# hdmilight-Duo.net
KiCad netlist of a schematic drawn in EAGLE
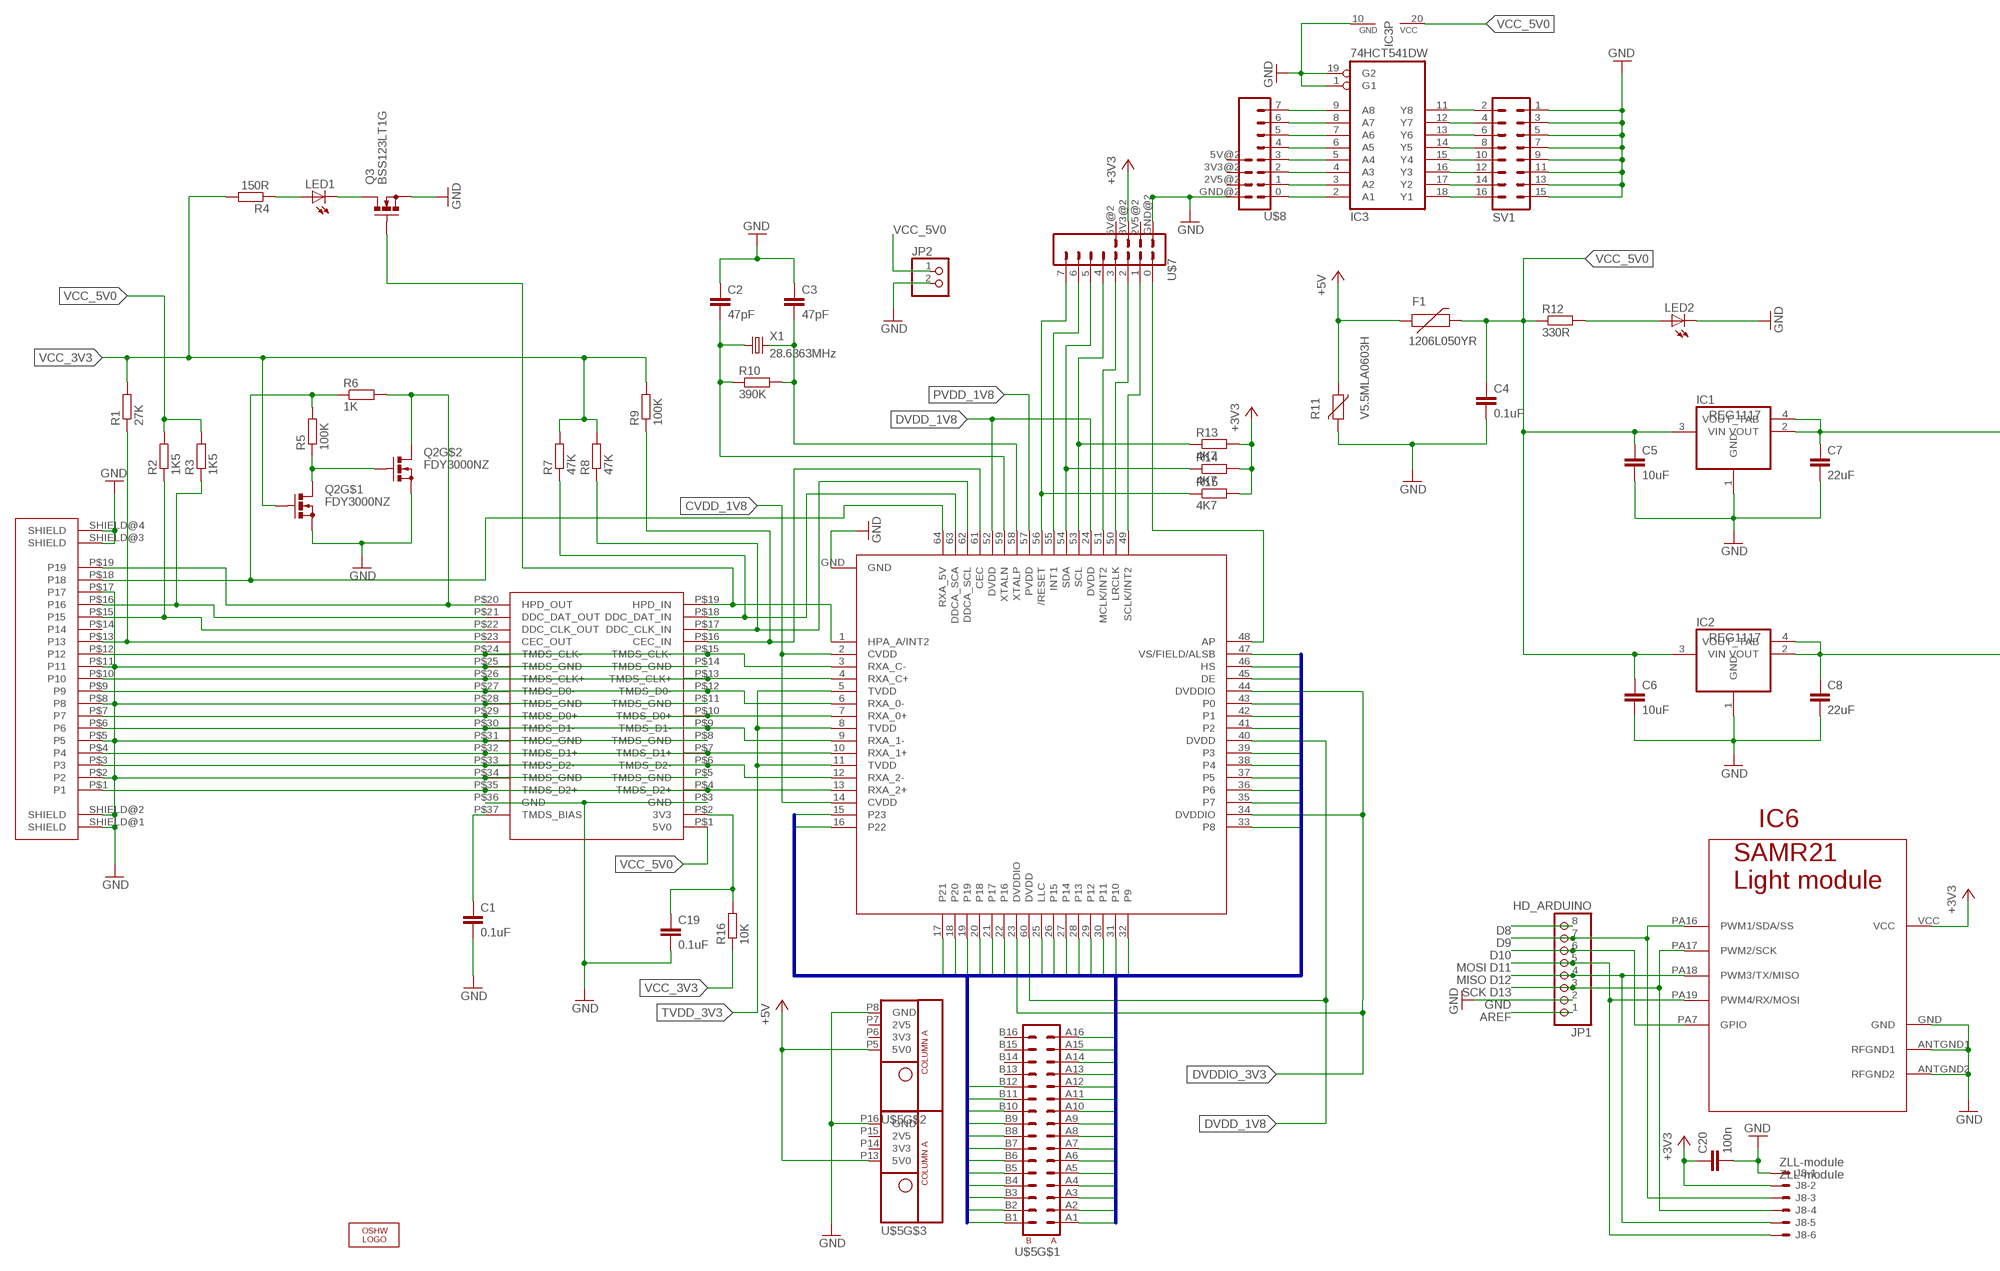
[diagram p0: schematic, sheet 1, part 1 of 2]
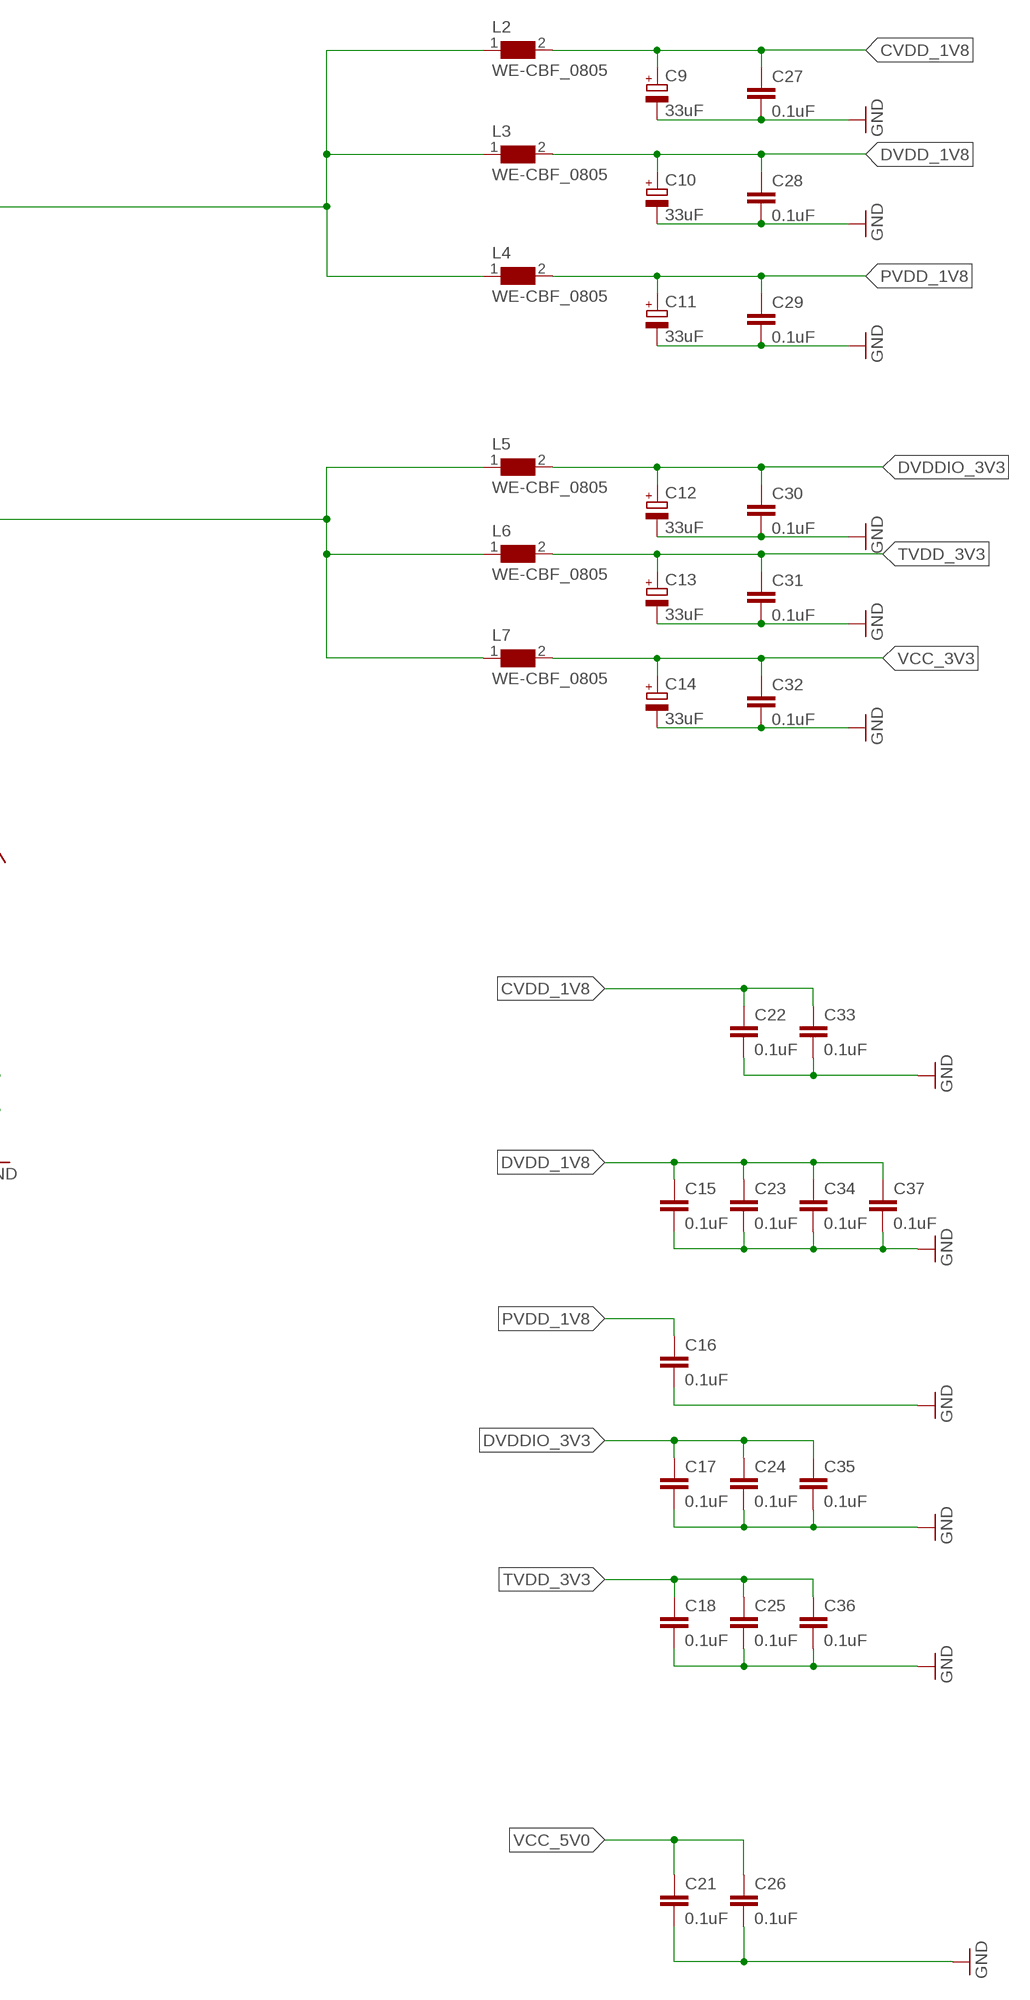
[diagram p1: schematic, sheet 1, part 2 of 2]

(export (version "E")
  (design (tool "Eeschema 10.0.6"))
  (components
    (comp (ref "C1")
      (value "0.1uF")
      (footprint "eagle-import:C0603")
      (libsource (lib "eagle-import") (part "resistor_C-EUC0603"))
    )
    (comp (ref "C2")
      (value "47pF")
      (footprint "eagle-import:C0603")
      (libsource (lib "eagle-import") (part "resistor_C-EUC0603"))
    )
    (comp (ref "C3")
      (value "47pF")
      (footprint "eagle-import:C0603")
      (libsource (lib "eagle-import") (part "resistor_C-EUC0603"))
    )
    (comp (ref "C4")
      (value "0.1uF")
      (footprint "eagle-import:C0603")
      (libsource (lib "eagle-import") (part "resistor_C-EUC0603"))
    )
    (comp (ref "C5")
      (value "10uF")
      (footprint "eagle-import:C1210")
      (libsource (lib "eagle-import") (part "resistor_C-EUC1210"))
    )
    (comp (ref "C6")
      (value "10uF")
      (footprint "eagle-import:C1210")
      (libsource (lib "eagle-import") (part "resistor_C-EUC1210"))
    )
    (comp (ref "C7")
      (value "22uF")
      (footprint "eagle-import:C1206")
      (libsource (lib "eagle-import") (part "resistor_C-EUC1206"))
    )
    (comp (ref "C8")
      (value "22uF")
      (footprint "eagle-import:C1206")
      (libsource (lib "eagle-import") (part "resistor_C-EUC1206"))
    )
    (comp (ref "C9")
      (value "33uF")
      (footprint "eagle-import:SMC_B")
      (libsource (lib "eagle-import") (part "CPOL-EUSMCB"))
    )
    (comp (ref "C10")
      (value "33uF")
      (footprint "eagle-import:SMC_B")
      (libsource (lib "eagle-import") (part "CPOL-EUSMCB"))
    )
    (comp (ref "C11")
      (value "33uF")
      (footprint "eagle-import:SMC_B")
      (libsource (lib "eagle-import") (part "CPOL-EUSMCB"))
    )
    (comp (ref "C12")
      (value "33uF")
      (footprint "eagle-import:SMC_B")
      (libsource (lib "eagle-import") (part "CPOL-EUSMCB"))
    )
    (comp (ref "C13")
      (value "33uF")
      (footprint "eagle-import:SMC_B")
      (libsource (lib "eagle-import") (part "CPOL-EUSMCB"))
    )
    (comp (ref "C14")
      (value "33uF")
      (footprint "eagle-import:SMC_B")
      (libsource (lib "eagle-import") (part "CPOL-EUSMCB"))
    )
    (comp (ref "C15")
      (value "0.1uF")
      (footprint "eagle-import:C0402")
      (libsource (lib "eagle-import") (part "resistor_C-EUC0402"))
    )
    (comp (ref "C16")
      (value "0.1uF")
      (footprint "eagle-import:C0603")
      (libsource (lib "eagle-import") (part "resistor_C-EUC0603"))
    )
    (comp (ref "C17")
      (value "0.1uF")
      (footprint "eagle-import:C0603")
      (libsource (lib "eagle-import") (part "resistor_C-EUC0603"))
    )
    (comp (ref "C18")
      (value "0.1uF")
      (footprint "eagle-import:C0402")
      (libsource (lib "eagle-import") (part "resistor_C-EUC0402"))
    )
    (comp (ref "C19")
      (value "0.1uF")
      (footprint "eagle-import:C0603")
      (libsource (lib "eagle-import") (part "resistor_C-EUC0603"))
    )
    (comp (ref "C20")
      (value "100n")
      (footprint "eagle-import:C0603K")
      (libsource (lib "eagle-import") (part "C-EUC0603K"))
    )
    (comp (ref "C21")
      (value "0.1uF")
      (footprint "eagle-import:C0603")
      (libsource (lib "eagle-import") (part "resistor_C-EUC0603"))
    )
    (comp (ref "C22")
      (value "0.1uF")
      (footprint "eagle-import:C0603")
      (libsource (lib "eagle-import") (part "resistor_C-EUC0603"))
    )
    (comp (ref "C23")
      (value "0.1uF")
      (footprint "eagle-import:C0402")
      (libsource (lib "eagle-import") (part "resistor_C-EUC0402"))
    )
    (comp (ref "C24")
      (value "0.1uF")
      (footprint "eagle-import:C0603")
      (libsource (lib "eagle-import") (part "resistor_C-EUC0603"))
    )
    (comp (ref "C25")
      (value "0.1uF")
      (footprint "eagle-import:C0402")
      (libsource (lib "eagle-import") (part "resistor_C-EUC0402"))
    )
    (comp (ref "C26")
      (value "0.1uF")
      (footprint "eagle-import:C0603")
      (libsource (lib "eagle-import") (part "resistor_C-EUC0603"))
    )
    (comp (ref "C27")
      (value "0.1uF")
      (footprint "eagle-import:C0603")
      (libsource (lib "eagle-import") (part "resistor_C-EUC0603"))
    )
    (comp (ref "C28")
      (value "0.1uF")
      (footprint "eagle-import:C0603")
      (libsource (lib "eagle-import") (part "resistor_C-EUC0603"))
    )
    (comp (ref "C29")
      (value "0.1uF")
      (footprint "eagle-import:C0603")
      (libsource (lib "eagle-import") (part "resistor_C-EUC0603"))
    )
    (comp (ref "C30")
      (value "0.1uF")
      (footprint "eagle-import:C0603")
      (libsource (lib "eagle-import") (part "resistor_C-EUC0603"))
    )
    (comp (ref "C31")
      (value "0.1uF")
      (footprint "eagle-import:C0603")
      (libsource (lib "eagle-import") (part "resistor_C-EUC0603"))
    )
    (comp (ref "C32")
      (value "0.1uF")
      (footprint "eagle-import:C0603")
      (libsource (lib "eagle-import") (part "resistor_C-EUC0603"))
    )
    (comp (ref "C33")
      (value "0.1uF")
      (footprint "eagle-import:C0603")
      (libsource (lib "eagle-import") (part "resistor_C-EUC0603"))
    )
    (comp (ref "C34")
      (value "0.1uF")
      (footprint "eagle-import:C0402")
      (libsource (lib "eagle-import") (part "resistor_C-EUC0402"))
    )
    (comp (ref "C35")
      (value "0.1uF")
      (footprint "eagle-import:C0402")
      (libsource (lib "eagle-import") (part "resistor_C-EUC0402"))
    )
    (comp (ref "C36")
      (value "0.1uF")
      (footprint "eagle-import:C0402")
      (libsource (lib "eagle-import") (part "resistor_C-EUC0402"))
    )
    (comp (ref "C37")
      (value "0.1uF")
      (footprint "eagle-import:C0402")
      (libsource (lib "eagle-import") (part "resistor_C-EUC0402"))
    )
    (comp (ref "F1")
      (value "1206L050YR")
      (footprint "eagle-import:PTC-1206")
      (libsource (lib "eagle-import") (part "PTCSMD"))
    )
    (comp (ref "IC1")
      (value "REG1117")
      (footprint "eagle-import:SOT223")
      (libsource (lib "eagle-import") (part "REG1117"))
    )
    (comp (ref "IC2")
      (value "REG1117")
      (footprint "eagle-import:SOT223")
      (libsource (lib "eagle-import") (part "REG1117"))
    )
    (comp (ref "IC3")
      (value "74HCT541DW")
      (footprint "eagle-import:SO20W")
      (libsource (lib "eagle-import") (part "74541DWHCT"))
    )
    (comp (ref "IC4")
      (value "ADV7611")
      (footprint "eagle-import:TQFP64-10X10")
      (libsource (lib "eagle-import") (part "ADV7611"))
    )
    (comp (ref "IC5")
      (value "TPD12S520")
      (footprint "eagle-import:TSSOP38")
      (libsource (lib "eagle-import") (part "IP4776CZ38"))
    )
    (comp (ref "IC6")
      (value "SAMR21-MODLL")
      (footprint "eagle-import:SAMR21-LLMOD")
      (libsource (lib "eagle-import") (part "SAMR21-MODLL"))
    )
    (comp (ref "J1")
      (value "FCI_HDMI_SOCKET_10029449-001RCF")
      (footprint "eagle-import:FCI_HDMI_SOCKET_10029449-001RCF")
      (libsource (lib "eagle-import") (part "FCI_HDMI_SOCKET_10029449-001RCF"))
    )
    (comp (ref "J8")
      (value "ZLL-module")
      (footprint "eagle-import:331-06")
      (libsource (lib "eagle-import") (part "331-06"))
    )
    (comp (ref "JP1")
      (value "HD_ARDUINO")
      (footprint "eagle-import:1X08_OCT")
      (libsource (lib "eagle-import") (part "PINHD-1X8/OCT"))
    )
    (comp (ref "JP2")
      (value "PINHD-1X2/OCT")
      (footprint "eagle-import:1X02_OCT")
      (libsource (lib "eagle-import") (part "PINHD-1X2/OCT"))
    )
    (comp (ref "L2")
      (value "WE-CBF_0805")
      (footprint "eagle-import:0805")
      (libsource (lib "eagle-import") (part "WE-CBF_0805"))
    )
    (comp (ref "L3")
      (value "WE-CBF_0805")
      (footprint "eagle-import:0805")
      (libsource (lib "eagle-import") (part "WE-CBF_0805"))
    )
    (comp (ref "L4")
      (value "WE-CBF_0805")
      (footprint "eagle-import:0805")
      (libsource (lib "eagle-import") (part "WE-CBF_0805"))
    )
    (comp (ref "L5")
      (value "WE-CBF_0805")
      (footprint "eagle-import:0805")
      (libsource (lib "eagle-import") (part "WE-CBF_0805"))
    )
    (comp (ref "L6")
      (value "WE-CBF_0805")
      (footprint "eagle-import:0805")
      (libsource (lib "eagle-import") (part "WE-CBF_0805"))
    )
    (comp (ref "L7")
      (value "WE-CBF_0805")
      (footprint "eagle-import:0805")
      (libsource (lib "eagle-import") (part "WE-CBF_0805"))
    )
    (comp (ref "LED1")
      (value "LEDCHIP-LED0805")
      (footprint "eagle-import:CHIP-LED0805")
      (libsource (lib "eagle-import") (part "LEDCHIP-LED0805"))
    )
    (comp (ref "LED2")
      (value "LEDCHIP-LED0805")
      (footprint "eagle-import:CHIP-LED0805")
      (libsource (lib "eagle-import") (part "LEDCHIP-LED0805"))
    )
    (comp (ref "LOGO1")
      (value "OSHW_LOGO_FILLX0200-NT")
      (footprint "eagle-import:OSHW_FILLX200_NOTEXT")
      (libsource (lib "eagle-import") (part "OSHW_LOGO_FILLX0200-NT"))
    )
    (comp (ref "Q2")
      (value "FDY3000NZ")
      (footprint "eagle-import:SC89-6")
      (libsource (lib "eagle-import") (part "FDY3000NZ"))
    )
    (comp (ref "Q3")
      (value "BSS123LT1G")
      (footprint "eagle-import:SOT23")
      (libsource (lib "eagle-import") (part "BSS123LT1G"))
    )
    (comp (ref "R1")
      (value "27K")
      (footprint "eagle-import:R0603")
      (libsource (lib "eagle-import") (part "R-EU_R0603"))
    )
    (comp (ref "R2")
      (value "1K5")
      (footprint "eagle-import:R0603")
      (libsource (lib "eagle-import") (part "R-EU_R0603"))
    )
    (comp (ref "R3")
      (value "1K5")
      (footprint "eagle-import:R0603")
      (libsource (lib "eagle-import") (part "R-EU_R0603"))
    )
    (comp (ref "R4")
      (value "150R")
      (footprint "eagle-import:R0603")
      (libsource (lib "eagle-import") (part "R-EU_R0603"))
    )
    (comp (ref "R5")
      (value "100K")
      (footprint "eagle-import:R0603")
      (libsource (lib "eagle-import") (part "R-EU_R0603"))
    )
    (comp (ref "R6")
      (value "1K")
      (footprint "eagle-import:R0603")
      (libsource (lib "eagle-import") (part "R-EU_R0603"))
    )
    (comp (ref "R7")
      (value "47K")
      (footprint "eagle-import:R0603")
      (libsource (lib "eagle-import") (part "R-EU_R0603"))
    )
    (comp (ref "R8")
      (value "47K")
      (footprint "eagle-import:R0603")
      (libsource (lib "eagle-import") (part "R-EU_R0603"))
    )
    (comp (ref "R9")
      (value "100K")
      (footprint "eagle-import:R0603")
      (libsource (lib "eagle-import") (part "R-EU_R0603"))
    )
    (comp (ref "R10")
      (value "390K")
      (footprint "eagle-import:R0603")
      (libsource (lib "eagle-import") (part "R-EU_R0603"))
    )
    (comp (ref "R11")
      (value "V5.5MLA0603H")
      (footprint "eagle-import:CT_CN0603")
      (libsource (lib "eagle-import") (part "VARISTORCN0603"))
    )
    (comp (ref "R12")
      (value "330R")
      (footprint "eagle-import:R0603")
      (libsource (lib "eagle-import") (part "R-EU_R0603"))
    )
    (comp (ref "R13")
      (value "4K7")
      (footprint "eagle-import:R0603")
      (libsource (lib "eagle-import") (part "R-EU_R0603"))
    )
    (comp (ref "R14")
      (value "4K7")
      (footprint "eagle-import:R0603")
      (libsource (lib "eagle-import") (part "R-EU_R0603"))
    )
    (comp (ref "R15")
      (value "4K7")
      (footprint "eagle-import:R0603")
      (libsource (lib "eagle-import") (part "R-EU_R0603"))
    )
    (comp (ref "R16")
      (value "10K")
      (footprint "eagle-import:R0603")
      (libsource (lib "eagle-import") (part "R-EU_R0603"))
    )
    (comp (ref "SV1")
      (value "MA08-2")
      (footprint "eagle-import:MA08-2")
      (libsource (lib "eagle-import") (part "MA08-2"))
    )
    (comp (ref "U$5")
      (value "WING32_HALF")
      (footprint "eagle-import:WING32_HALF_NOHOLES")
      (libsource (lib "eagle-import") (part "WING32_HALF"))
    )
    (comp (ref "U$7")
      (value "WING8WING8_NOHOLES")
      (footprint "eagle-import:WINGSIDE_8BIT_NOHOLES")
      (libsource (lib "eagle-import") (part "WING8WING8_NOHOLES"))
    )
    (comp (ref "U$8")
      (value "WING8WING8_NOHOLES")
      (footprint "eagle-import:WINGSIDE_8BIT_NOHOLES")
      (libsource (lib "eagle-import") (part "WING8WING8_NOHOLES"))
    )
    (comp (ref "X1")
      (value "28.6363MHz")
      (footprint "eagle-import:SM49")
      (libsource (lib "eagle-import") (part "CRYSTALSM49"))
    )
  )
  (nets
    (net (code "1") (name "+3V3") (class "Default")
      (node (ref "C20") (pin "1") (pinfunction "1_1") (pintype "passive"))
      (node (ref "IC6") (pin "VCC") (pinfunction "VCC_VCC") (pintype "bidirectional"))
      (node (ref "J8") (pin "3") (pinfunction "S_3") (pintype "passive"))
      (node (ref "R13") (pin "2") (pinfunction "2_2") (pintype "passive"))
      (node (ref "R14") (pin "2") (pinfunction "2_2") (pintype "passive"))
      (node (ref "R15") (pin "2") (pinfunction "2_2") (pintype "passive"))
      (node (ref "U$7") (pin "3V3@2") (pinfunction "3V3_3V3@2") (pintype "passive"))
    )
    (net (code "2") (name "+5V") (class "Default")
      (node (ref "F1") (pin "1") (pinfunction "1_1") (pintype "bidirectional"))
      (node (ref "R11") (pin "1") (pinfunction "1_1") (pintype "passive"))
      (node (ref "U$5") (pin "P13") (pinfunction "5V0_P13") (pintype "passive"))
      (node (ref "U$5") (pin "P5") (pinfunction "5V0_P5") (pintype "passive"))
    )
    (net (code "3") (name "/AREF") (class "Default")
      (node (ref "JP1") (pin "1") (pinfunction "1_1") (pintype "passive"))
    )
    (net (code "4") (name "/D8") (class "Default")
      (node (ref "JP1") (pin "8") (pinfunction "8_8") (pintype "passive"))
    )
    (net (code "5") (name "/D9") (class "Default")
      (node (ref "IC6") (pin "PA16") (pinfunction "PWM1/SDA/SS_PA16") (pintype "bidirectional"))
      (node (ref "J8") (pin "5") (pinfunction "S_5") (pintype "passive"))
      (node (ref "JP1") (pin "7") (pinfunction "7_7") (pintype "passive"))
    )
    (net (code "6") (name "/D10") (class "Default")
      (node (ref "IC6") (pin "PA7") (pinfunction "GPIO_PA7") (pintype "bidirectional"))
      (node (ref "JP1") (pin "6") (pinfunction "6_6") (pintype "passive"))
    )
    (net (code "7") (name "/D11") (class "Default")
      (node (ref "IC6") (pin "PA19") (pinfunction "PWM4/RX/MOSI_PA19") (pintype "bidirectional"))
      (node (ref "J8") (pin "11") (pinfunction "S_11") (pintype "passive"))
      (node (ref "JP1") (pin "5") (pinfunction "5_5") (pintype "passive"))
    )
    (net (code "8") (name "/D12") (class "Default")
      (node (ref "IC6") (pin "PA18") (pinfunction "PWM3/TX/MISO_PA18") (pintype "bidirectional"))
      (node (ref "J8") (pin "9") (pinfunction "S_9") (pintype "passive"))
      (node (ref "JP1") (pin "4") (pinfunction "4_4") (pintype "passive"))
    )
    (net (code "9") (name "/D13") (class "Default")
      (node (ref "IC6") (pin "PA17") (pinfunction "PWM2/SCK_PA17") (pintype "bidirectional"))
      (node (ref "J8") (pin "7") (pinfunction "S_7") (pintype "passive"))
      (node (ref "JP1") (pin "3") (pinfunction "3_3") (pintype "passive"))
    )
    (net (code "10") (name "/DE") (class "Default")
      (node (ref "IC4") (pin "45") (pinfunction "DE_45") (pintype "bidirectional"))
      (node (ref "U$5") (pin "B2") (pinfunction "B2_B2") (pintype "bidirectional"))
    )
    (net (code "11") (name "/HS") (class "Default")
      (node (ref "IC4") (pin "46") (pinfunction "HS_46") (pintype "bidirectional"))
      (node (ref "U$5") (pin "A1") (pinfunction "A1_A1") (pintype "bidirectional"))
    )
    (net (code "12") (name "/LLC") (class "Default")
      (node (ref "IC4") (pin "25") (pinfunction "LLC_25") (pintype "bidirectional"))
      (node (ref "U$5") (pin "A14") (pinfunction "A14_A14") (pintype "bidirectional"))
    )
    (net (code "13") (name "/P0") (class "Default")
      (node (ref "IC4") (pin "43") (pinfunction "P0_43") (pintype "bidirectional"))
      (node (ref "U$5") (pin "A2") (pinfunction "A2_A2") (pintype "bidirectional"))
    )
    (net (code "14") (name "/P1") (class "Default")
      (node (ref "IC4") (pin "42") (pinfunction "P1_42") (pintype "bidirectional"))
      (node (ref "U$5") (pin "B3") (pinfunction "B3_B3") (pintype "bidirectional"))
    )
    (net (code "15") (name "/P2") (class "Default")
      (node (ref "IC4") (pin "41") (pinfunction "P2_41") (pintype "bidirectional"))
      (node (ref "U$5") (pin "A3") (pinfunction "A3_A3") (pintype "bidirectional"))
    )
    (net (code "16") (name "/P3") (class "Default")
      (node (ref "IC4") (pin "39") (pinfunction "P3_39") (pintype "bidirectional"))
      (node (ref "U$5") (pin "B4") (pinfunction "B4_B4") (pintype "bidirectional"))
    )
    (net (code "17") (name "/P4") (class "Default")
      (node (ref "IC4") (pin "38") (pinfunction "P4_38") (pintype "bidirectional"))
      (node (ref "U$5") (pin "A4") (pinfunction "A4_A4") (pintype "bidirectional"))
    )
    (net (code "18") (name "/P5") (class "Default")
      (node (ref "IC4") (pin "37") (pinfunction "P5_37") (pintype "bidirectional"))
      (node (ref "U$5") (pin "B5") (pinfunction "B5_B5") (pintype "bidirectional"))
    )
    (net (code "19") (name "/P6") (class "Default")
      (node (ref "IC4") (pin "36") (pinfunction "P6_36") (pintype "bidirectional"))
      (node (ref "U$5") (pin "A5") (pinfunction "A5_A5") (pintype "bidirectional"))
    )
    (net (code "20") (name "/P7") (class "Default")
      (node (ref "IC4") (pin "35") (pinfunction "P7_35") (pintype "bidirectional"))
      (node (ref "U$5") (pin "B6") (pinfunction "B6_B6") (pintype "bidirectional"))
    )
    (net (code "21") (name "/P8") (class "Default")
      (node (ref "IC4") (pin "33") (pinfunction "P8_33") (pintype "bidirectional"))
      (node (ref "U$5") (pin "A6") (pinfunction "A6_A6") (pintype "bidirectional"))
    )
    (net (code "22") (name "/P9") (class "Default")
      (node (ref "IC4") (pin "32") (pinfunction "P9_32") (pintype "bidirectional"))
      (node (ref "U$5") (pin "B7") (pinfunction "B7_B7") (pintype "bidirectional"))
    )
    (net (code "23") (name "/P10") (class "Default")
      (node (ref "IC4") (pin "31") (pinfunction "P10_31") (pintype "bidirectional"))
      (node (ref "U$5") (pin "A7") (pinfunction "A7_A7") (pintype "bidirectional"))
    )
    (net (code "24") (name "/P11") (class "Default")
      (node (ref "IC4") (pin "30") (pinfunction "P11_30") (pintype "bidirectional"))
      (node (ref "U$5") (pin "B8") (pinfunction "B8_B8") (pintype "bidirectional"))
    )
    (net (code "25") (name "/P12") (class "Default")
      (node (ref "IC4") (pin "29") (pinfunction "P12_29") (pintype "bidirectional"))
      (node (ref "U$5") (pin "A8") (pinfunction "A8_A8") (pintype "bidirectional"))
    )
    (net (code "26") (name "/P13") (class "Default")
      (node (ref "IC4") (pin "28") (pinfunction "P13_28") (pintype "bidirectional"))
      (node (ref "U$5") (pin "B9") (pinfunction "B9_B9") (pintype "bidirectional"))
    )
    (net (code "27") (name "/P14") (class "Default")
      (node (ref "IC4") (pin "27") (pinfunction "P14_27") (pintype "bidirectional"))
      (node (ref "U$5") (pin "A9") (pinfunction "A9_A9") (pintype "bidirectional"))
    )
    (net (code "28") (name "/P15") (class "Default")
      (node (ref "IC4") (pin "26") (pinfunction "P15_26") (pintype "bidirectional"))
      (node (ref "U$5") (pin "B10") (pinfunction "B10_B10") (pintype "bidirectional"))
    )
    (net (code "29") (name "/P16") (class "Default")
      (node (ref "IC4") (pin "22") (pinfunction "P16_22") (pintype "bidirectional"))
      (node (ref "U$5") (pin "A10") (pinfunction "A10_A10") (pintype "bidirectional"))
    )
    (net (code "30") (name "/P17") (class "Default")
      (node (ref "IC4") (pin "21") (pinfunction "P17_21") (pintype "bidirectional"))
      (node (ref "U$5") (pin "B11") (pinfunction "B11_B11") (pintype "bidirectional"))
    )
    (net (code "31") (name "/P18") (class "Default")
      (node (ref "IC4") (pin "20") (pinfunction "P18_20") (pintype "bidirectional"))
      (node (ref "U$5") (pin "A11") (pinfunction "A11_A11") (pintype "bidirectional"))
    )
    (net (code "32") (name "/P19") (class "Default")
      (node (ref "IC4") (pin "19") (pinfunction "P19_19") (pintype "bidirectional"))
      (node (ref "U$5") (pin "B12") (pinfunction "B12_B12") (pintype "bidirectional"))
    )
    (net (code "33") (name "/P20") (class "Default")
      (node (ref "IC4") (pin "18") (pinfunction "P20_18") (pintype "bidirectional"))
      (node (ref "U$5") (pin "A12") (pinfunction "A12_A12") (pintype "bidirectional"))
    )
    (net (code "34") (name "/P21") (class "Default")
      (node (ref "IC4") (pin "17") (pinfunction "P21_17") (pintype "bidirectional"))
      (node (ref "U$5") (pin "A13") (pinfunction "A13_A13") (pintype "bidirectional"))
    )
    (net (code "35") (name "/P22") (class "Default")
      (node (ref "IC4") (pin "16") (pinfunction "P22_16") (pintype "bidirectional"))
      (node (ref "U$5") (pin "A15") (pinfunction "A15_A15") (pintype "bidirectional"))
    )
    (net (code "36") (name "/P23") (class "Default")
      (node (ref "IC4") (pin "15") (pinfunction "P23_15") (pintype "bidirectional"))
      (node (ref "U$5") (pin "A16") (pinfunction "A16_A16") (pintype "bidirectional"))
    )
    (net (code "37") (name "/VS") (class "Default")
      (node (ref "IC4") (pin "47") (pinfunction "VS/FIELD/ALSB_47") (pintype "bidirectional"))
      (node (ref "U$5") (pin "B1") (pinfunction "B1_B1") (pintype "bidirectional"))
    )
    (net (code "38") (name "CVDD_1V8") (class "Default")
      (node (ref "C22") (pin "1") (pinfunction "1_1") (pintype "passive"))
      (node (ref "C27") (pin "1") (pinfunction "1_1") (pintype "passive"))
      (node (ref "C33") (pin "1") (pinfunction "1_1") (pintype "passive"))
      (node (ref "C9") (pin "+") (pinfunction "+_+") (pintype "passive"))
      (node (ref "IC4") (pin "14") (pinfunction "CVDD_14") (pintype "bidirectional"))
      (node (ref "IC4") (pin "2") (pinfunction "CVDD_2") (pintype "bidirectional"))
      (node (ref "L2") (pin "2") (pinfunction "2_2") (pintype "passive"))
    )
    (net (code "39") (name "DVDDIO_3V3") (class "Default")
      (node (ref "C12") (pin "+") (pinfunction "+_+") (pintype "passive"))
      (node (ref "C17") (pin "1") (pinfunction "1_1") (pintype "passive"))
      (node (ref "C24") (pin "1") (pinfunction "1_1") (pintype "passive"))
      (node (ref "C30") (pin "1") (pinfunction "1_1") (pintype "passive"))
      (node (ref "C35") (pin "1") (pinfunction "1_1") (pintype "passive"))
      (node (ref "IC4") (pin "23") (pinfunction "DVDDIO_23") (pintype "bidirectional"))
      (node (ref "IC4") (pin "34") (pinfunction "DVDDIO_34") (pintype "bidirectional"))
      (node (ref "IC4") (pin "44") (pinfunction "DVDDIO_44") (pintype "bidirectional"))
      (node (ref "L5") (pin "2") (pinfunction "2_2") (pintype "passive"))
    )
    (net (code "40") (name "DVDD_1V8") (class "Default")
      (node (ref "C10") (pin "+") (pinfunction "+_+") (pintype "passive"))
      (node (ref "C15") (pin "1") (pinfunction "1_1") (pintype "passive"))
      (node (ref "C23") (pin "1") (pinfunction "1_1") (pintype "passive"))
      (node (ref "C28") (pin "1") (pinfunction "1_1") (pintype "passive"))
      (node (ref "C34") (pin "1") (pinfunction "1_1") (pintype "passive"))
      (node (ref "C37") (pin "1") (pinfunction "1_1") (pintype "passive"))
      (node (ref "IC4") (pin "24") (pinfunction "DVDD_24") (pintype "bidirectional"))
      (node (ref "IC4") (pin "40") (pinfunction "DVDD_40") (pintype "bidirectional"))
      (node (ref "IC4") (pin "52") (pinfunction "DVDD_52") (pintype "bidirectional"))
      (node (ref "IC4") (pin "60") (pinfunction "DVDD_60") (pintype "bidirectional"))
      (node (ref "L3") (pin "2") (pinfunction "2_2") (pintype "passive"))
    )
    (net (code "41") (name "GND") (class "Default")
      (node (ref "C1") (pin "2") (pinfunction "2_2") (pintype "passive"))
      (node (ref "C10") (pin "-") (pinfunction "-_-") (pintype "passive"))
      (node (ref "C11") (pin "-") (pinfunction "-_-") (pintype "passive"))
      (node (ref "C12") (pin "-") (pinfunction "-_-") (pintype "passive"))
      (node (ref "C13") (pin "-") (pinfunction "-_-") (pintype "passive"))
      (node (ref "C14") (pin "-") (pinfunction "-_-") (pintype "passive"))
      (node (ref "C15") (pin "2") (pinfunction "2_2") (pintype "passive"))
      (node (ref "C16") (pin "2") (pinfunction "2_2") (pintype "passive"))
      (node (ref "C17") (pin "2") (pinfunction "2_2") (pintype "passive"))
      (node (ref "C18") (pin "2") (pinfunction "2_2") (pintype "passive"))
      (node (ref "C19") (pin "2") (pinfunction "2_2") (pintype "passive"))
      (node (ref "C2") (pin "1") (pinfunction "1_1") (pintype "passive"))
      (node (ref "C20") (pin "2") (pinfunction "2_2") (pintype "passive"))
      (node (ref "C21") (pin "2") (pinfunction "2_2") (pintype "passive"))
      (node (ref "C22") (pin "2") (pinfunction "2_2") (pintype "passive"))
      (node (ref "C23") (pin "2") (pinfunction "2_2") (pintype "passive"))
      (node (ref "C24") (pin "2") (pinfunction "2_2") (pintype "passive"))
      (node (ref "C25") (pin "2") (pinfunction "2_2") (pintype "passive"))
      (node (ref "C26") (pin "2") (pinfunction "2_2") (pintype "passive"))
      (node (ref "C27") (pin "2") (pinfunction "2_2") (pintype "passive"))
      (node (ref "C28") (pin "2") (pinfunction "2_2") (pintype "passive"))
      (node (ref "C29") (pin "2") (pinfunction "2_2") (pintype "passive"))
      (node (ref "C3") (pin "1") (pinfunction "1_1") (pintype "passive"))
      (node (ref "C30") (pin "2") (pinfunction "2_2") (pintype "passive"))
      (node (ref "C31") (pin "2") (pinfunction "2_2") (pintype "passive"))
      (node (ref "C32") (pin "2") (pinfunction "2_2") (pintype "passive"))
      (node (ref "C33") (pin "2") (pinfunction "2_2") (pintype "passive"))
      (node (ref "C34") (pin "2") (pinfunction "2_2") (pintype "passive"))
      (node (ref "C35") (pin "2") (pinfunction "2_2") (pintype "passive"))
      (node (ref "C36") (pin "2") (pinfunction "2_2") (pintype "passive"))
      (node (ref "C37") (pin "2") (pinfunction "2_2") (pintype "passive"))
      (node (ref "C4") (pin "2") (pinfunction "2_2") (pintype "passive"))
      (node (ref "C5") (pin "2") (pinfunction "2_2") (pintype "passive"))
      (node (ref "C6") (pin "2") (pinfunction "2_2") (pintype "passive"))
      (node (ref "C7") (pin "2") (pinfunction "2_2") (pintype "passive"))
      (node (ref "C8") (pin "2") (pinfunction "2_2") (pintype "passive"))
      (node (ref "C9") (pin "-") (pinfunction "-_-") (pintype "passive"))
      (node (ref "IC1") (pin "1") (pinfunction "GND_1") (pintype "power_in"))
      (node (ref "IC2") (pin "1") (pinfunction "GND_1") (pintype "power_in"))
      (node (ref "IC3") (pin "1") (pinfunction "G1_1") (pintype "input"))
      (node (ref "IC3") (pin "10") (pinfunction "GND_10") (pintype "power_in"))
      (node (ref "IC3") (pin "19") (pinfunction "G2_19") (pintype "input"))
      (node (ref "IC4") (pin "GND") (pinfunction "GND_GND") (pintype "bidirectional"))
      (node (ref "IC5") (pin "P$11") (pinfunction "TMDS_GND_P$11") (pintype "bidirectional"))
      (node (ref "IC5") (pin "P$14") (pinfunction "TMDS_GND_P$14") (pintype "bidirectional"))
      (node (ref "IC5") (pin "P$25") (pinfunction "TMDS_GND_P$25") (pintype "bidirectional"))
      (node (ref "IC5") (pin "P$28") (pinfunction "TMDS_GND_P$28") (pintype "bidirectional"))
      (node (ref "IC5") (pin "P$3") (pinfunction "GND_P$3") (pintype "bidirectional"))
      (node (ref "IC5") (pin "P$31") (pinfunction "TMDS_GND_P$31") (pintype "bidirectional"))
      (node (ref "IC5") (pin "P$34") (pinfunction "TMDS_GND_P$34") (pintype "bidirectional"))
      (node (ref "IC5") (pin "P$36") (pinfunction "GND_P$36") (pintype "bidirectional"))
      (node (ref "IC5") (pin "P$5") (pinfunction "TMDS_GND_P$5") (pintype "bidirectional"))
      (node (ref "IC5") (pin "P$8") (pinfunction "TMDS_GND_P$8") (pintype "bidirectional"))
      (node (ref "IC6") (pin "ANTGND1") (pinfunction "RFGND1_ANTGND1") (pintype "bidirectional"))
      (node (ref "IC6") (pin "ANTGND2") (pinfunction "RFGND2_ANTGND2") (pintype "bidirectional"))
      (node (ref "IC6") (pin "GND") (pinfunction "GND_GND") (pintype "bidirectional"))
      (node (ref "J1") (pin "P$11") (pinfunction "P11_P$11") (pintype "bidirectional"))
      (node (ref "J1") (pin "P$17") (pinfunction "P17_P$17") (pintype "bidirectional"))
      (node (ref "J1") (pin "P$2") (pinfunction "P2_P$2") (pintype "bidirectional"))
      (node (ref "J1") (pin "P$5") (pinfunction "P5_P$5") (pintype "bidirectional"))
      (node (ref "J1") (pin "P$8") (pinfunction "P8_P$8") (pintype "bidirectional"))
      (node (ref "J1") (pin "SHIELD@1") (pinfunction "SHIELD_SHIELD@1") (pintype "bidirectional"))
      (node (ref "J1") (pin "SHIELD@2") (pinfunction "SHIELD_SHIELD@2") (pintype "bidirectional"))
      (node (ref "J1") (pin "SHIELD@3") (pinfunction "SHIELD_SHIELD@3") (pintype "bidirectional"))
      (node (ref "J1") (pin "SHIELD@4") (pinfunction "SHIELD_SHIELD@4") (pintype "bidirectional"))
      (node (ref "J8") (pin "1") (pinfunction "S_1") (pintype "passive"))
      (node (ref "JP1") (pin "2") (pinfunction "2_2") (pintype "passive"))
      (node (ref "JP2") (pin "2") (pinfunction "2_2") (pintype "passive"))
      (node (ref "LED2") (pin "C") (pinfunction "C_C") (pintype "passive"))
      (node (ref "Q2") (pin "P$1") (pinfunction "S_P$1") (pintype "passive"))
      (node (ref "Q2") (pin "P$4") (pinfunction "S_P$4") (pintype "passive"))
      (node (ref "Q3") (pin "2") (pinfunction "S_2") (pintype "passive"))
      (node (ref "R11") (pin "2") (pinfunction "2_2") (pintype "passive"))
      (node (ref "SV1") (pin "1") (pinfunction "1_1") (pintype "passive"))
      (node (ref "SV1") (pin "11") (pinfunction "11_11") (pintype "passive"))
      (node (ref "SV1") (pin "13") (pinfunction "13_13") (pintype "passive"))
      (node (ref "SV1") (pin "15") (pinfunction "15_15") (pintype "passive"))
      (node (ref "SV1") (pin "3") (pinfunction "3_3") (pintype "passive"))
      (node (ref "SV1") (pin "5") (pinfunction "5_5") (pintype "passive"))
      (node (ref "SV1") (pin "7") (pinfunction "7_7") (pintype "passive"))
      (node (ref "SV1") (pin "9") (pinfunction "9_9") (pintype "passive"))
      (node (ref "U$5") (pin "P16") (pinfunction "GND_P16") (pintype "power_in"))
      (node (ref "U$5") (pin "P8") (pinfunction "GND_P8") (pintype "power_in"))
      (node (ref "U$7") (pin "GND@2") (pinfunction "GND_GND@2") (pintype "passive"))
      (node (ref "U$8") (pin "GND@2") (pinfunction "GND_GND@2") (pintype "passive"))
    )
    (net (code "42") (name "Net-(IC1-VOUT)") (class "Default")
      (node (ref "C7") (pin "1") (pinfunction "1_1") (pintype "passive"))
      (node (ref "IC1") (pin "2") (pinfunction "VOUT_2") (pintype "output"))
      (node (ref "IC1") (pin "4") (pinfunction "VOUT_TAB_4") (pintype "output"))
      (node (ref "L2") (pin "1") (pinfunction "1_1") (pintype "passive"))
      (node (ref "L3") (pin "1") (pinfunction "1_1") (pintype "passive"))
      (node (ref "L4") (pin "1") (pinfunction "1_1") (pintype "passive"))
    )
    (net (code "43") (name "Net-(IC2-VOUT)") (class "Default")
      (node (ref "C8") (pin "1") (pinfunction "1_1") (pintype "passive"))
      (node (ref "IC2") (pin "2") (pinfunction "VOUT_2") (pintype "output"))
      (node (ref "IC2") (pin "4") (pinfunction "VOUT_TAB_4") (pintype "output"))
      (node (ref "L5") (pin "1") (pinfunction "1_1") (pintype "passive"))
      (node (ref "L6") (pin "1") (pinfunction "1_1") (pintype "passive"))
      (node (ref "L7") (pin "1") (pinfunction "1_1") (pintype "passive"))
    )
    (net (code "44") (name "Net-(IC3A-A1)") (class "Default")
      (node (ref "IC3") (pin "2") (pinfunction "A1_2") (pintype "input"))
      (node (ref "U$8") (pin "0") (pinfunction "1_0") (pintype "passive"))
    )
    (net (code "45") (name "Net-(IC3A-A2)") (class "Default")
      (node (ref "IC3") (pin "3") (pinfunction "A2_3") (pintype "input"))
      (node (ref "U$8") (pin "1") (pinfunction "2_1") (pintype "passive"))
    )
    (net (code "46") (name "Net-(IC3A-A3)") (class "Default")
      (node (ref "IC3") (pin "4") (pinfunction "A3_4") (pintype "input"))
      (node (ref "U$8") (pin "2") (pinfunction "3_2") (pintype "passive"))
    )
    (net (code "47") (name "Net-(IC3A-A4)") (class "Default")
      (node (ref "IC3") (pin "5") (pinfunction "A4_5") (pintype "input"))
      (node (ref "U$8") (pin "3") (pinfunction "4_3") (pintype "passive"))
    )
    (net (code "48") (name "Net-(IC3A-A5)") (class "Default")
      (node (ref "IC3") (pin "6") (pinfunction "A5_6") (pintype "input"))
      (node (ref "U$8") (pin "4") (pinfunction "5_4") (pintype "passive"))
    )
    (net (code "49") (name "Net-(IC3A-A6)") (class "Default")
      (node (ref "IC3") (pin "7") (pinfunction "A6_7") (pintype "input"))
      (node (ref "U$8") (pin "5") (pinfunction "6_5") (pintype "passive"))
    )
    (net (code "50") (name "Net-(IC3A-A7)") (class "Default")
      (node (ref "IC3") (pin "8") (pinfunction "A7_8") (pintype "input"))
      (node (ref "U$8") (pin "6") (pinfunction "7_6") (pintype "passive"))
    )
    (net (code "51") (name "Net-(IC3A-A8)") (class "Default")
      (node (ref "IC3") (pin "9") (pinfunction "A8_9") (pintype "input"))
      (node (ref "U$8") (pin "7") (pinfunction "8_7") (pintype "passive"))
    )
    (net (code "52") (name "Net-(IC3A-Y1)") (class "Default")
      (node (ref "IC3") (pin "18") (pinfunction "Y1_18") (pintype "tri_state"))
      (node (ref "SV1") (pin "16") (pinfunction "16_16") (pintype "passive"))
    )
    (net (code "53") (name "Net-(IC3A-Y2)") (class "Default")
      (node (ref "IC3") (pin "17") (pinfunction "Y2_17") (pintype "tri_state"))
      (node (ref "SV1") (pin "14") (pinfunction "14_14") (pintype "passive"))
    )
    (net (code "54") (name "Net-(IC3A-Y3)") (class "Default")
      (node (ref "IC3") (pin "16") (pinfunction "Y3_16") (pintype "tri_state"))
      (node (ref "SV1") (pin "12") (pinfunction "12_12") (pintype "passive"))
    )
    (net (code "55") (name "Net-(IC3A-Y4)") (class "Default")
      (node (ref "IC3") (pin "15") (pinfunction "Y4_15") (pintype "tri_state"))
      (node (ref "SV1") (pin "10") (pinfunction "10_10") (pintype "passive"))
    )
    (net (code "56") (name "Net-(IC3A-Y5)") (class "Default")
      (node (ref "IC3") (pin "14") (pinfunction "Y5_14") (pintype "tri_state"))
      (node (ref "SV1") (pin "8") (pinfunction "8_8") (pintype "passive"))
    )
    (net (code "57") (name "Net-(IC3A-Y6)") (class "Default")
      (node (ref "IC3") (pin "13") (pinfunction "Y6_13") (pintype "tri_state"))
      (node (ref "SV1") (pin "6") (pinfunction "6_6") (pintype "passive"))
    )
    (net (code "58") (name "Net-(IC3A-Y7)") (class "Default")
      (node (ref "IC3") (pin "12") (pinfunction "Y7_12") (pintype "tri_state"))
      (node (ref "SV1") (pin "4") (pinfunction "4_4") (pintype "passive"))
    )
    (net (code "59") (name "Net-(IC3A-Y8)") (class "Default")
      (node (ref "IC3") (pin "11") (pinfunction "Y8_11") (pintype "tri_state"))
      (node (ref "SV1") (pin "2") (pinfunction "2_2") (pintype "passive"))
    )
    (net (code "60") (name "Net-(IC4-AP)") (class "Default")
      (node (ref "IC4") (pin "48") (pinfunction "AP_48") (pintype "bidirectional"))
      (node (ref "U$7") (pin "0") (pinfunction "1_0") (pintype "passive"))
    )
    (net (code "61") (name "Net-(IC4-CEC)") (class "Default")
      (node (ref "IC4") (pin "61") (pinfunction "CEC_61") (pintype "bidirectional"))
      (node (ref "IC5") (pin "P$16") (pinfunction "CEC_IN_P$16") (pintype "bidirectional"))
      (node (ref "R9") (pin "1") (pinfunction "1_1") (pintype "passive"))
    )
    (net (code "62") (name "Net-(IC4-DDCA_SCA)") (class "Default")
      (node (ref "IC4") (pin "63") (pinfunction "DDCA_SCA_63") (pintype "bidirectional"))
      (node (ref "IC5") (pin "P$18") (pinfunction "DDC_DAT_IN_P$18") (pintype "bidirectional"))
      (node (ref "R7") (pin "1") (pinfunction "1_1") (pintype "passive"))
    )
    (net (code "63") (name "Net-(IC4-DDCA_SCL)") (class "Default")
      (node (ref "IC4") (pin "62") (pinfunction "DDCA_SCL_62") (pintype "bidirectional"))
      (node (ref "IC5") (pin "P$17") (pinfunction "DDC_CLK_IN_P$17") (pintype "bidirectional"))
      (node (ref "R8") (pin "1") (pinfunction "1_1") (pintype "passive"))
    )
    (net (code "64") (name "Net-(IC4-HPA_A{slash}INT2)") (class "Default")
      (node (ref "IC4") (pin "1") (pinfunction "HPA_A/INT2_1") (pintype "bidirectional"))
      (node (ref "IC5") (pin "P$19") (pinfunction "HPD_IN_P$19") (pintype "bidirectional"))
      (node (ref "Q3") (pin "1") (pinfunction "G_1") (pintype "passive"))
    )
    (net (code "65") (name "Net-(IC4-INT1)") (class "Default")
      (node (ref "IC4") (pin "55") (pinfunction "INT1_55") (pintype "bidirectional"))
      (node (ref "U$7") (pin "6") (pinfunction "7_6") (pintype "passive"))
    )
    (net (code "66") (name "Net-(IC4-LRCLK)") (class "Default")
      (node (ref "IC4") (pin "50") (pinfunction "LRCLK_50") (pintype "bidirectional"))
      (node (ref "U$7") (pin "2") (pinfunction "3_2") (pintype "passive"))
    )
    (net (code "67") (name "Net-(IC4-MCLK{slash}INT2)") (class "Default")
      (node (ref "IC4") (pin "51") (pinfunction "MCLK/INT2_51") (pintype "bidirectional"))
      (node (ref "U$7") (pin "3") (pinfunction "4_3") (pintype "passive"))
    )
    (net (code "68") (name "Net-(IC4-RXA_0+)") (class "Default")
      (node (ref "IC4") (pin "7") (pinfunction "RXA_0+_7") (pintype "bidirectional"))
      (node (ref "IC5") (pin "P$10") (pinfunction "TMDS_D0+_P$10") (pintype "bidirectional"))
      (node (ref "IC5") (pin "P$29") (pinfunction "TMDS_D0+_P$29") (pintype "bidirectional"))
      (node (ref "J1") (pin "P$7") (pinfunction "P7_P$7") (pintype "bidirectional"))
    )
    (net (code "69") (name "Net-(IC4-RXA_0-)") (class "Default")
      (node (ref "IC4") (pin "6") (pinfunction "RXA_0-_6") (pintype "bidirectional"))
      (node (ref "IC5") (pin "P$12") (pinfunction "TMDS_D0-_P$12") (pintype "bidirectional"))
      (node (ref "IC5") (pin "P$27") (pinfunction "TMDS_D0-_P$27") (pintype "bidirectional"))
      (node (ref "J1") (pin "P$9") (pinfunction "P9_P$9") (pintype "bidirectional"))
    )
    (net (code "70") (name "Net-(IC4-RXA_1+)") (class "Default")
      (node (ref "IC4") (pin "10") (pinfunction "RXA_1+_10") (pintype "bidirectional"))
      (node (ref "IC5") (pin "P$32") (pinfunction "TMDS_D1+_P$32") (pintype "bidirectional"))
      (node (ref "IC5") (pin "P$7") (pinfunction "TMDS_D1+_P$7") (pintype "bidirectional"))
      (node (ref "J1") (pin "P$4") (pinfunction "P4_P$4") (pintype "bidirectional"))
    )
    (net (code "71") (name "Net-(IC4-RXA_1-)") (class "Default")
      (node (ref "IC4") (pin "9") (pinfunction "RXA_1-_9") (pintype "bidirectional"))
      (node (ref "IC5") (pin "P$30") (pinfunction "TMDS_D1-_P$30") (pintype "bidirectional"))
      (node (ref "IC5") (pin "P$9") (pinfunction "TMDS_D1-_P$9") (pintype "bidirectional"))
      (node (ref "J1") (pin "P$6") (pinfunction "P6_P$6") (pintype "bidirectional"))
    )
    (net (code "72") (name "Net-(IC4-RXA_2+)") (class "Default")
      (node (ref "IC4") (pin "13") (pinfunction "RXA_2+_13") (pintype "bidirectional"))
      (node (ref "IC5") (pin "P$35") (pinfunction "TMDS_D2+_P$35") (pintype "bidirectional"))
      (node (ref "IC5") (pin "P$4") (pinfunction "TMDS_D2+_P$4") (pintype "bidirectional"))
      (node (ref "J1") (pin "P$1") (pinfunction "P1_P$1") (pintype "bidirectional"))
    )
    (net (code "73") (name "Net-(IC4-RXA_2-)") (class "Default")
      (node (ref "IC4") (pin "12") (pinfunction "RXA_2-_12") (pintype "bidirectional"))
      (node (ref "IC5") (pin "P$33") (pinfunction "TMDS_D2-_P$33") (pintype "bidirectional"))
      (node (ref "IC5") (pin "P$6") (pinfunction "TMDS_D2-_P$6") (pintype "bidirectional"))
      (node (ref "J1") (pin "P$3") (pinfunction "P3_P$3") (pintype "bidirectional"))
    )
    (net (code "74") (name "Net-(IC4-RXA_5V)") (class "Default")
      (node (ref "IC4") (pin "64") (pinfunction "RXA_5V_64") (pintype "bidirectional"))
      (node (ref "J1") (pin "P$18") (pinfunction "P18_P$18") (pintype "bidirectional"))
      (node (ref "R5") (pin "2") (pinfunction "2_2") (pintype "passive"))
      (node (ref "R6") (pin "1") (pinfunction "1_1") (pintype "passive"))
    )
    (net (code "75") (name "Net-(IC4-RXA_C+)") (class "Default")
      (node (ref "IC4") (pin "4") (pinfunction "RXA_C+_4") (pintype "bidirectional"))
      (node (ref "IC5") (pin "P$13") (pinfunction "TMDS_CLK+_P$13") (pintype "bidirectional"))
      (node (ref "IC5") (pin "P$26") (pinfunction "TMDS_CLK+_P$26") (pintype "bidirectional"))
      (node (ref "J1") (pin "P$10") (pinfunction "P10_P$10") (pintype "bidirectional"))
    )
    (net (code "76") (name "Net-(IC4-RXA_C-)") (class "Default")
      (node (ref "IC4") (pin "3") (pinfunction "RXA_C-_3") (pintype "bidirectional"))
      (node (ref "IC5") (pin "P$15") (pinfunction "TMDS_CLK-_P$15") (pintype "bidirectional"))
      (node (ref "IC5") (pin "P$24") (pinfunction "TMDS_CLK-_P$24") (pintype "bidirectional"))
      (node (ref "J1") (pin "P$12") (pinfunction "P12_P$12") (pintype "bidirectional"))
    )
    (net (code "77") (name "Net-(IC4-SCL)") (class "Default")
      (node (ref "IC4") (pin "53") (pinfunction "SCL_53") (pintype "bidirectional"))
      (node (ref "R13") (pin "1") (pinfunction "1_1") (pintype "passive"))
      (node (ref "U$7") (pin "4") (pinfunction "5_4") (pintype "passive"))
    )
    (net (code "78") (name "Net-(IC4-SCLK{slash}INT2)") (class "Default")
      (node (ref "IC4") (pin "49") (pinfunction "SCLK/INT2_49") (pintype "bidirectional"))
      (node (ref "U$7") (pin "1") (pinfunction "2_1") (pintype "passive"))
    )
    (net (code "79") (name "Net-(IC4-SDA)") (class "Default")
      (node (ref "IC4") (pin "54") (pinfunction "SDA_54") (pintype "bidirectional"))
      (node (ref "R14") (pin "1") (pinfunction "1_1") (pintype "passive"))
      (node (ref "U$7") (pin "5") (pinfunction "6_5") (pintype "passive"))
    )
    (net (code "80") (name "Net-(IC4-XTALN)") (class "Default")
      (node (ref "C2") (pin "2") (pinfunction "2_2") (pintype "passive"))
      (node (ref "IC4") (pin "59") (pinfunction "XTALN_59") (pintype "bidirectional"))
      (node (ref "R10") (pin "1") (pinfunction "1_1") (pintype "passive"))
      (node (ref "X1") (pin "1") (pinfunction "1_1") (pintype "passive"))
    )
    (net (code "81") (name "Net-(IC4-XTALP)") (class "Default")
      (node (ref "C3") (pin "2") (pinfunction "2_2") (pintype "passive"))
      (node (ref "IC4") (pin "58") (pinfunction "XTALP_58") (pintype "bidirectional"))
      (node (ref "R10") (pin "2") (pinfunction "2_2") (pintype "passive"))
      (node (ref "X1") (pin "2") (pinfunction "2_2") (pintype "passive"))
    )
    (net (code "82") (name "Net-(IC4-{slash}RESET)") (class "Default")
      (node (ref "IC4") (pin "56") (pinfunction "/RESET_56") (pintype "bidirectional"))
      (node (ref "R15") (pin "1") (pinfunction "1_1") (pintype "passive"))
      (node (ref "U$7") (pin "7") (pinfunction "8_7") (pintype "passive"))
    )
    (net (code "83") (name "Net-(IC5-3V3)") (class "Default")
      (node (ref "C19") (pin "1") (pinfunction "1_1") (pintype "passive"))
      (node (ref "IC5") (pin "P$2") (pinfunction "3V3_P$2") (pintype "bidirectional"))
      (node (ref "R16") (pin "2") (pinfunction "2_2") (pintype "passive"))
    )
    (net (code "84") (name "Net-(IC5-CEC_OUT)") (class "Default")
      (node (ref "IC5") (pin "P$23") (pinfunction "CEC_OUT_P$23") (pintype "bidirectional"))
      (node (ref "J1") (pin "P$13") (pinfunction "P13_P$13") (pintype "bidirectional"))
      (node (ref "R1") (pin "1") (pinfunction "1_1") (pintype "passive"))
    )
    (net (code "85") (name "Net-(IC5-DDC_CLK_OUT)") (class "Default")
      (node (ref "IC5") (pin "P$22") (pinfunction "DDC_CLK_OUT_P$22") (pintype "bidirectional"))
      (node (ref "J1") (pin "P$15") (pinfunction "P15_P$15") (pintype "bidirectional"))
      (node (ref "R2") (pin "1") (pinfunction "1_1") (pintype "passive"))
    )
    (net (code "86") (name "Net-(IC5-DDC_DAT_OUT)") (class "Default")
      (node (ref "IC5") (pin "P$21") (pinfunction "DDC_DAT_OUT_P$21") (pintype "bidirectional"))
      (node (ref "J1") (pin "P$16") (pinfunction "P16_P$16") (pintype "bidirectional"))
      (node (ref "R3") (pin "1") (pinfunction "1_1") (pintype "passive"))
    )
    (net (code "87") (name "Net-(IC5-HPD_OUT)") (class "Default")
      (node (ref "IC5") (pin "P$20") (pinfunction "HPD_OUT_P$20") (pintype "bidirectional"))
      (node (ref "J1") (pin "P$19") (pinfunction "P19_P$19") (pintype "bidirectional"))
      (node (ref "Q2") (pin "P$3") (pinfunction "D_P$3") (pintype "passive"))
      (node (ref "R6") (pin "2") (pinfunction "2_2") (pintype "passive"))
    )
    (net (code "88") (name "Net-(IC5-TMDS_BIAS)") (class "Default")
      (node (ref "C1") (pin "1") (pinfunction "1_1") (pintype "passive"))
      (node (ref "IC5") (pin "P$37") (pinfunction "TMDS_BIAS_P$37") (pintype "bidirectional"))
    )
    (net (code "89") (name "Net-(LED1-PadA)") (class "Default")
      (node (ref "LED1") (pin "A") (pinfunction "A_A") (pintype "passive"))
      (node (ref "R4") (pin "1") (pinfunction "1_1") (pintype "passive"))
    )
    (net (code "90") (name "Net-(LED2-PadA)") (class "Default")
      (node (ref "LED2") (pin "A") (pinfunction "A_A") (pintype "passive"))
      (node (ref "R12") (pin "2") (pinfunction "2_2") (pintype "passive"))
    )
    (net (code "91") (name "Net-(Q2A-D)") (class "Default")
      (node (ref "Q2") (pin "P$5") (pinfunction "G_P$5") (pintype "passive"))
      (node (ref "Q2") (pin "P$6") (pinfunction "D_P$6") (pintype "passive"))
      (node (ref "R5") (pin "1") (pinfunction "1_1") (pintype "passive"))
    )
    (net (code "92") (name "Net-(Q3-D)") (class "Default")
      (node (ref "LED1") (pin "C") (pinfunction "C_C") (pintype "passive"))
      (node (ref "Q3") (pin "3") (pinfunction "D_3") (pintype "passive"))
    )
    (net (code "93") (name "PVDD_1V8") (class "Default")
      (node (ref "C11") (pin "+") (pinfunction "+_+") (pintype "passive"))
      (node (ref "C16") (pin "1") (pinfunction "1_1") (pintype "passive"))
      (node (ref "C29") (pin "1") (pinfunction "1_1") (pintype "passive"))
      (node (ref "IC4") (pin "57") (pinfunction "PVDD_57") (pintype "bidirectional"))
      (node (ref "L4") (pin "2") (pinfunction "2_2") (pintype "passive"))
    )
    (net (code "94") (name "TVDD_3V3") (class "Default")
      (node (ref "C13") (pin "+") (pinfunction "+_+") (pintype "passive"))
      (node (ref "C18") (pin "1") (pinfunction "1_1") (pintype "passive"))
      (node (ref "C25") (pin "1") (pinfunction "1_1") (pintype "passive"))
      (node (ref "C31") (pin "1") (pinfunction "1_1") (pintype "passive"))
      (node (ref "C36") (pin "1") (pinfunction "1_1") (pintype "passive"))
      (node (ref "IC4") (pin "11") (pinfunction "TVDD_11") (pintype "bidirectional"))
      (node (ref "IC4") (pin "5") (pinfunction "TVDD_5") (pintype "bidirectional"))
      (node (ref "IC4") (pin "8") (pinfunction "TVDD_8") (pintype "bidirectional"))
      (node (ref "L6") (pin "2") (pinfunction "2_2") (pintype "passive"))
    )
    (net (code "95") (name "VCC_3V3") (class "Default")
      (node (ref "C14") (pin "+") (pinfunction "+_+") (pintype "passive"))
      (node (ref "C32") (pin "1") (pinfunction "1_1") (pintype "passive"))
      (node (ref "L7") (pin "2") (pinfunction "2_2") (pintype "passive"))
      (node (ref "Q2") (pin "P$2") (pinfunction "G_P$2") (pintype "passive"))
      (node (ref "R1") (pin "2") (pinfunction "2_2") (pintype "passive"))
      (node (ref "R16") (pin "1") (pinfunction "1_1") (pintype "passive"))
      (node (ref "R4") (pin "2") (pinfunction "2_2") (pintype "passive"))
      (node (ref "R7") (pin "2") (pinfunction "2_2") (pintype "passive"))
      (node (ref "R8") (pin "2") (pinfunction "2_2") (pintype "passive"))
      (node (ref "R9") (pin "2") (pinfunction "2_2") (pintype "passive"))
    )
    (net (code "96") (name "VCC_5V0") (class "Default")
      (node (ref "C21") (pin "1") (pinfunction "1_1") (pintype "passive"))
      (node (ref "C26") (pin "1") (pinfunction "1_1") (pintype "passive"))
      (node (ref "C4") (pin "1") (pinfunction "1_1") (pintype "passive"))
      (node (ref "C5") (pin "1") (pinfunction "1_1") (pintype "passive"))
      (node (ref "C6") (pin "1") (pinfunction "1_1") (pintype "passive"))
      (node (ref "F1") (pin "2") (pinfunction "2_2") (pintype "bidirectional"))
      (node (ref "IC1") (pin "3") (pinfunction "VIN_3") (pintype "input"))
      (node (ref "IC2") (pin "3") (pinfunction "VIN_3") (pintype "input"))
      (node (ref "IC3") (pin "20") (pinfunction "VCC_20") (pintype "power_in"))
      (node (ref "IC5") (pin "P$1") (pinfunction "5V0_P$1") (pintype "bidirectional"))
      (node (ref "JP2") (pin "1") (pinfunction "1_1") (pintype "passive"))
      (node (ref "R12") (pin "1") (pinfunction "1_1") (pintype "passive"))
      (node (ref "R2") (pin "2") (pinfunction "2_2") (pintype "passive"))
      (node (ref "R3") (pin "2") (pinfunction "2_2") (pintype "passive"))
    )
    (net (code "97") (name "unconnected-(J1-P14-PadP$14)") (class "Default")
      (node (ref "J1") (pin "P$14") (pinfunction "P14_P$14") (pintype "bidirectional"))
    )
    (net (code "98") (name "unconnected-(U$5-PadB13)") (class "Default")
      (node (ref "U$5") (pin "B13") (pinfunction "B13_B13") (pintype "bidirectional"))
    )
    (net (code "99") (name "unconnected-(U$5-PadB14)") (class "Default")
      (node (ref "U$5") (pin "B14") (pinfunction "B14_B14") (pintype "bidirectional"))
    )
    (net (code "100") (name "unconnected-(U$5-PadB15)") (class "Default")
      (node (ref "U$5") (pin "B15") (pinfunction "B15_B15") (pintype "bidirectional"))
    )
    (net (code "101") (name "unconnected-(U$5-PadB16)") (class "Default")
      (node (ref "U$5") (pin "B16") (pinfunction "B16_B16") (pintype "bidirectional"))
    )
    (net (code "102") (name "unconnected-(U$5B-2V5-PadP7)") (class "Default")
      (node (ref "U$5") (pin "P7") (pinfunction "2V5_P7") (pintype "passive"))
    )
    (net (code "103") (name "unconnected-(U$5B-3V3-PadP6)") (class "Default")
      (node (ref "U$5") (pin "P6") (pinfunction "3V3_P6") (pintype "passive"))
    )
    (net (code "104") (name "unconnected-(U$5C-2V5-PadP15)") (class "Default")
      (node (ref "U$5") (pin "P15") (pinfunction "2V5_P15") (pintype "passive"))
    )
    (net (code "105") (name "unconnected-(U$5C-3V3-PadP14)") (class "Default")
      (node (ref "U$5") (pin "P14") (pinfunction "3V3_P14") (pintype "passive"))
    )
    (net (code "106") (name "unconnected-(U$7-2V5-Pad2V5@2)") (class "Default")
      (node (ref "U$7") (pin "2V5@2") (pinfunction "2V5_2V5@2") (pintype "passive"))
    )
    (net (code "107") (name "unconnected-(U$7-5V-Pad5V@2)") (class "Default")
      (node (ref "U$7") (pin "5V@2") (pinfunction "5V_5V@2") (pintype "passive"))
    )
    (net (code "108") (name "unconnected-(U$8-2V5-Pad2V5@2)") (class "Default")
      (node (ref "U$8") (pin "2V5@2") (pinfunction "2V5_2V5@2") (pintype "passive"))
    )
    (net (code "109") (name "unconnected-(U$8-3V3-Pad3V3@2)") (class "Default")
      (node (ref "U$8") (pin "3V3@2") (pinfunction "3V3_3V3@2") (pintype "passive"))
    )
    (net (code "110") (name "unconnected-(U$8-5V-Pad5V@2)") (class "Default")
      (node (ref "U$8") (pin "5V@2") (pinfunction "5V_5V@2") (pintype "passive"))
    )
  )
)
